# Schemat_ideowy.net
KiCad netlist of a schematic drawn in Altium Designer
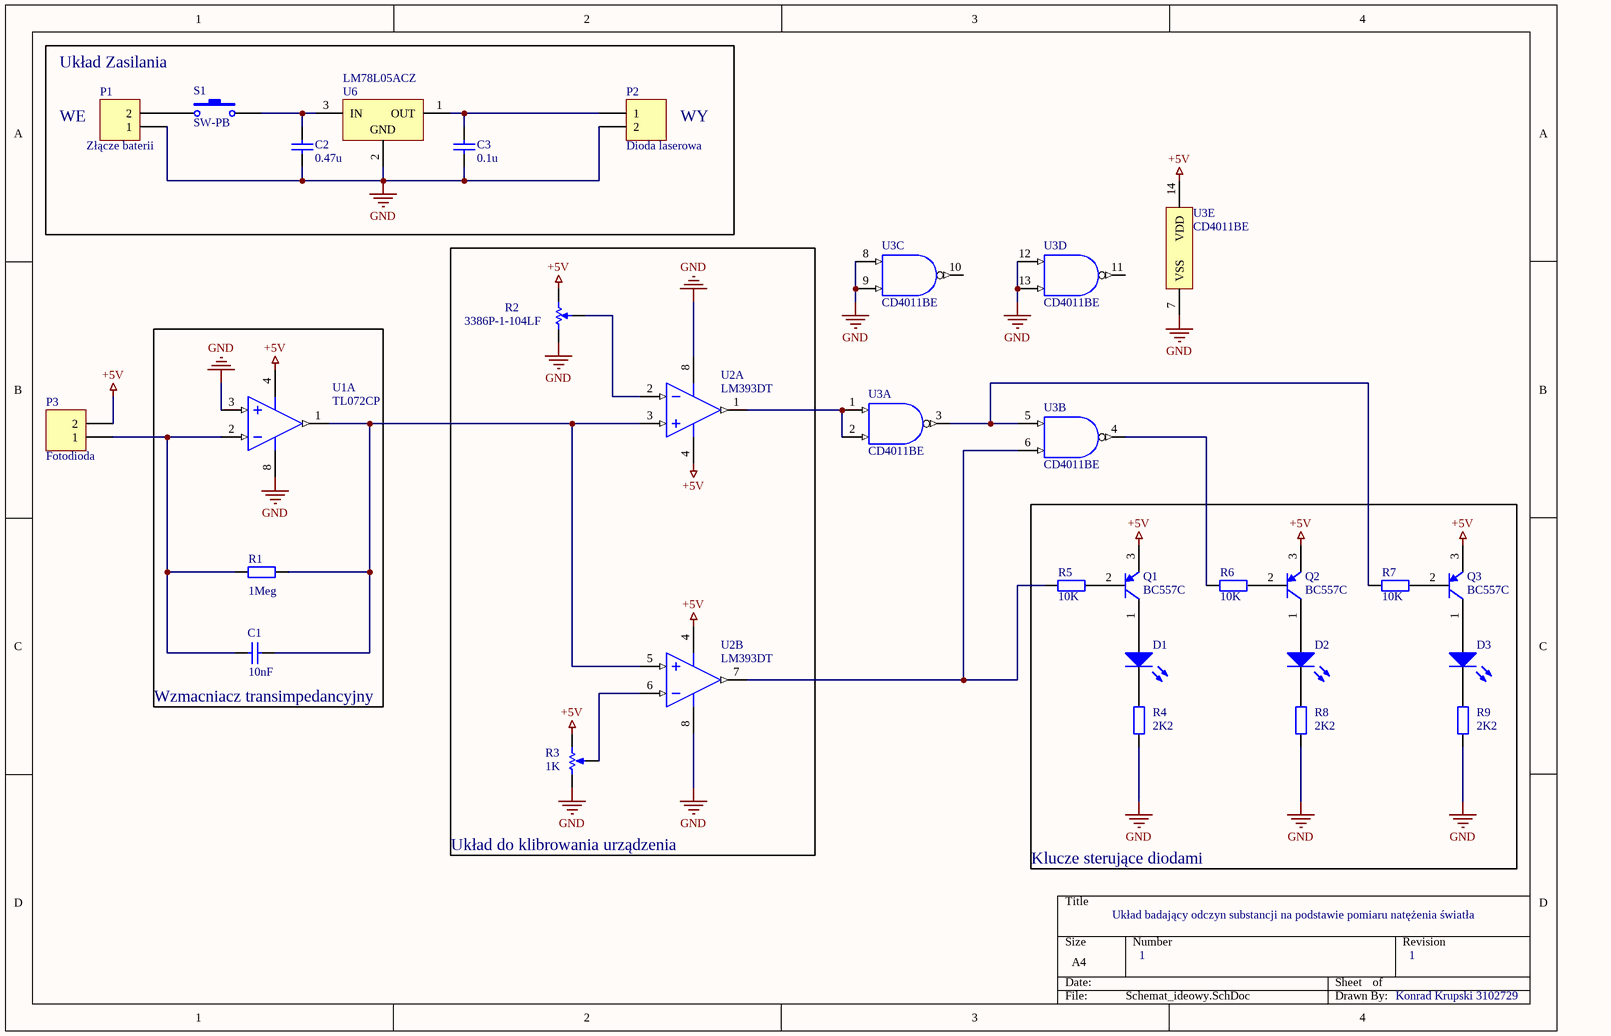
[diagram p0: Schemat_ideowy.SchDoc]

(export (version "E")
  (design (tool "Eeschema 10.0.6"))
  (components
    (comp (ref "C1")
      (value "10nF")
      (footprint "RAD-0.3")
      (description "Capacitor")
      (fields (field (name "Comment") "Cap") (field (name "PUBLISHER") "Altium Limited"))
      (libsource (lib "Miscellaneous Devices") (part "Cap"))
    )
    (comp (ref "C2")
      (value "0.47u")
      (footprint "RAD-0.3")
      (description "Capacitor")
      (fields (field (name "Comment") "Cap") (field (name "PUBLISHER") "Altium Limited"))
      (libsource (lib "Miscellaneous Devices") (part "Cap"))
    )
    (comp (ref "C3")
      (value "0.1u")
      (footprint "RAD-0.3")
      (description "Capacitor")
      (fields (field (name "Comment") "Cap") (field (name "PUBLISHER") "Altium Limited"))
      (libsource (lib "Miscellaneous Devices") (part "Cap"))
    )
    (comp (ref "D1")
      (value "LED3")
      (footprint "3.5X2.8X1.9")
      (description "Typical BLUE SiC LED")
      (fields (field (name "PUBLISHER") "Altium Limited"))
      (libsource (lib "Miscellaneous Devices") (part "LED3"))
    )
    (comp (ref "D2")
      (value "LED2")
      (footprint "3.2X1.6X1.1")
      (description "Typical RED, GREEN, YELLOW, AMBER GaAs LED")
      (fields (field (name "PUBLISHER") "Altium Limited"))
      (libsource (lib "Miscellaneous Devices") (part "LED2"))
    )
    (comp (ref "D3")
      (value "LED2")
      (footprint "3.2X1.6X1.1")
      (description "Typical RED, GREEN, YELLOW, AMBER GaAs LED")
      (fields (field (name "PUBLISHER") "Altium Limited"))
      (libsource (lib "Miscellaneous Devices") (part "LED2"))
    )
    (comp (ref "P1")
      (value "Złącze baterii")
      (footprint "HDR1X2H")
      (description "Header, 2-Pin, Right Angle")
      (fields (field (name "PUBLISHER") "Altium Limited"))
      (libsource (lib "Miscellaneous Connectors") (part "Header 2H"))
    )
    (comp (ref "P2")
      (value "Header 2H")
      (footprint "HDR1X2H")
      (description "Header, 2-Pin, Right Angle")
      (fields (field (name "PUBLISHER") "Altium Limited"))
      (libsource (lib "") (part "Header 2H_1"))
    )
    (comp (ref "P3")
      (value "Fotodioda")
      (footprint "HDR1X2H")
      (description "Header, 2-Pin, Right Angle")
      (fields (field (name "PUBLISHER") "Altium Limited"))
      (libsource (lib "Miscellaneous Connectors") (part "Header 2H"))
    )
    (comp (ref "Q1")
      (value "BC557C")
      (footprint "ONSC-TO-92-3-29-11")
      (description "Amplifier Transistor, PNP Silicon, 3-Pin TO-92, Bulk Box")
      (fields (field (name "MANUFACTURER") "On Semiconductor"))
      (libsource (lib "Altium Content Vault") (part "ONSC-PNP-C1B2E3-3"))
    )
    (comp (ref "Q2")
      (value "BC557C")
      (footprint "ONSC-TO-92-3-29-11")
      (description "Amplifier Transistor, PNP Silicon, 3-Pin TO-92, Bulk Box")
      (fields (field (name "MANUFACTURER") "On Semiconductor"))
      (libsource (lib "Altium Content Vault") (part "ONSC-PNP-C1B2E3-3"))
    )
    (comp (ref "Q3")
      (value "BC557C")
      (footprint "ONSC-TO-92-3-29-11")
      (description "Amplifier Transistor, PNP Silicon, 3-Pin TO-92, Bulk Box")
      (fields (field (name "MANUFACTURER") "On Semiconductor"))
      (libsource (lib "Altium Content Vault") (part "ONSC-PNP-C1B2E3-3"))
    )
    (comp (ref "R1")
      (value "1Meg")
      (footprint "AXIAL-0.4")
      (description "Resistor")
      (fields (field (name "Comment") "Res2") (field (name "PUBLISHER") "Altium Limited"))
      (libsource (lib "") (part "Res2_2"))
    )
    (comp (ref "R2")
      (value "3386P-1-104LF")
      (footprint "BOUR-3386P")
      (fields (field (name "TOLERANCE") "10%") (field (name "MANUFACTURER") "Bourns"))
      (libsource (lib "Altium Content Vault") (part "RES-ADJ-3_A"))
    )
    (comp (ref "R3")
      (value "1K")
      (footprint "VR5")
      (description "Potentiometer")
      (fields (field (name "Comment") "RPot") (field (name "PUBLISHER") "Altium Limited"))
      (libsource (lib "Miscellaneous Devices") (part "RPot"))
    )
    (comp (ref "R4")
      (value "2K2")
      (footprint "AXIAL-0.4")
      (description "Resistor")
      (fields (field (name "Comment") "Res2") (field (name "PUBLISHER") "Altium Limited"))
      (libsource (lib "") (part "Res2_1"))
    )
    (comp (ref "R5")
      (value "10K")
      (footprint "AXIAL-0.4")
      (description "Resistor")
      (fields (field (name "Comment") "Res2") (field (name "PUBLISHER") "Altium Limited"))
      (libsource (lib "Miscellaneous Devices") (part "Res2"))
    )
    (comp (ref "R6")
      (value "10K")
      (footprint "AXIAL-0.4")
      (description "Resistor")
      (fields (field (name "Comment") "Res2") (field (name "PUBLISHER") "Altium Limited"))
      (libsource (lib "Miscellaneous Devices") (part "Res2"))
    )
    (comp (ref "R7")
      (value "10K")
      (footprint "AXIAL-0.4")
      (description "Resistor")
      (fields (field (name "Comment") "Res2") (field (name "PUBLISHER") "Altium Limited"))
      (libsource (lib "Miscellaneous Devices") (part "Res2"))
    )
    (comp (ref "R8")
      (value "2K2")
      (footprint "AXIAL-0.4")
      (description "Resistor")
      (fields (field (name "Comment") "Res2") (field (name "PUBLISHER") "Altium Limited"))
      (libsource (lib "") (part "Res2_1"))
    )
    (comp (ref "R9")
      (value "2K2")
      (footprint "AXIAL-0.4")
      (description "Resistor")
      (fields (field (name "Comment") "Res2") (field (name "PUBLISHER") "Altium Limited"))
      (libsource (lib "") (part "Res2_1"))
    )
    (comp (ref "S1")
      (value "SW-PB")
      (footprint "SPST-2")
      (description "Switch")
      (fields (field (name "PUBLISHER") "Altium Limited"))
      (libsource (lib "Miscellaneous Devices") (part "SW-PB"))
    )
    (comp (ref "U1")
      (value "TL072CP")
      (footprint "P0008A")
      (fields (field (name "MANUFACTURER") "Texas Instruments"))
      (libsource (lib "Altium Content Vault") (part "TI-AMP-D6-2-8_D"))
    )
    (comp (ref "U2")
      (value "LM393DT")
      (footprint "STM-SO-8_D_L")
      (description "Low-Power, Dual-Voltage Comparator, 2 to 36 V, 0 to 70 degC, 8-Pin SOIC (SO), RoHS, Tape and Reel")
      (fields (field (name "MANUFACTURER") "STMicroelectronics"))
      (libsource (lib "Altium Content Vault") (part "STM-LM393-SO8"))
    )
    (comp (ref "U3")
      (value "CD4011BE")
      (footprint "N0014A")
      (description "CMOS Quad 2-Input NAND Gate, N0014A, TUBE")
      (fields
        (field (name "MANUFACTURER") "Texas Instruments")
        (field (name "GENERIC PART NUMBER") "CD4011B")
      )
      (libsource (lib "") (part "TI-NAND-4-2IN-14_A_1"))
    )
    (comp (ref "U6")
      (value "LM78L05ACZ")
      (footprint "Z03A")
      (description "3-Terminal Positive Regulators, 3-pin TO-92")
      (fields (field (name "MANUFACTURER") "National Semiconductor"))
      (libsource (lib "Altium Content Vault") (part "PM-REG-LM78L05-SIL3"))
    )
  )
  (nets
    (net (code "1") (name "+5V") (class "Default")
      (node (ref "P3") (pin "2") (pinfunction "2_2") (pintype "passive"))
      (node (ref "Q1") (pin "3") (pinfunction "E_3") (pintype "passive"))
      (node (ref "Q2") (pin "3") (pinfunction "E_3") (pintype "passive"))
      (node (ref "Q3") (pin "3") (pinfunction "E_3") (pintype "passive"))
      (node (ref "R2") (pin "3") (pinfunction "3_3") (pintype "passive"))
      (node (ref "R3") (pin "2") (pinfunction "BOT_2") (pintype "passive"))
      (node (ref "U1") (pin "4") (pinfunction "VCC-_4") (pintype "power_in"))
      (node (ref "U2") (pin "4") (pinfunction "VCC-_4") (pintype "power_in"))
      (node (ref "U3") (pin "14") (pinfunction "VDD_14") (pintype "power_in"))
    )
    (net (code "2") (name "GND") (class "Default")
      (node (ref "C2") (pin "1") (pinfunction "1_1") (pintype "passive"))
      (node (ref "C3") (pin "1") (pinfunction "1_1") (pintype "passive"))
      (node (ref "P1") (pin "1") (pinfunction "1_1") (pintype "passive"))
      (node (ref "P2") (pin "2") (pinfunction "2_2") (pintype "passive"))
      (node (ref "R2") (pin "1") (pinfunction "1_1") (pintype "passive"))
      (node (ref "R3") (pin "1") (pinfunction "TOP_1") (pintype "passive"))
      (node (ref "R4") (pin "1") (pinfunction "1_1") (pintype "passive"))
      (node (ref "R8") (pin "1") (pinfunction "1_1") (pintype "passive"))
      (node (ref "R9") (pin "1") (pinfunction "1_1") (pintype "passive"))
      (node (ref "U1") (pin "3") (pinfunction "IN1+_3") (pintype "input"))
      (node (ref "U1") (pin "8") (pinfunction "VCC+_8") (pintype "power_in"))
      (node (ref "U2") (pin "8") (pinfunction "VCC+_8") (pintype "power_in"))
      (node (ref "U3") (pin "12") (pinfunction "G_12") (pintype "input"))
      (node (ref "U3") (pin "13") (pinfunction "H_13") (pintype "input"))
      (node (ref "U3") (pin "7") (pinfunction "VSS_7") (pintype "power_in"))
      (node (ref "U3") (pin "8") (pinfunction "E_8") (pintype "input"))
      (node (ref "U3") (pin "9") (pinfunction "F_9") (pintype "input"))
      (node (ref "U6") (pin "2") (pinfunction "GND_2") (pintype "power_in"))
    )
    (net (code "3") (name "Net-(D1-A)") (class "Default")
      (node (ref "D1") (pin "1") (pinfunction "A_1") (pintype "passive"))
      (node (ref "Q1") (pin "1") (pinfunction "C_1") (pintype "passive"))
    )
    (net (code "4") (name "Net-(D1-K)") (class "Default")
      (node (ref "D1") (pin "2") (pinfunction "K_2") (pintype "passive"))
      (node (ref "R4") (pin "2") (pinfunction "2_2") (pintype "passive"))
    )
    (net (code "5") (name "Net-(D2-A)") (class "Default")
      (node (ref "D2") (pin "1") (pinfunction "A_1") (pintype "passive"))
      (node (ref "Q2") (pin "1") (pinfunction "C_1") (pintype "passive"))
    )
    (net (code "6") (name "Net-(D2-K)") (class "Default")
      (node (ref "D2") (pin "2") (pinfunction "K_2") (pintype "passive"))
      (node (ref "R8") (pin "2") (pinfunction "2_2") (pintype "passive"))
    )
    (net (code "7") (name "Net-(D3-A)") (class "Default")
      (node (ref "D3") (pin "1") (pinfunction "A_1") (pintype "passive"))
      (node (ref "Q3") (pin "1") (pinfunction "C_1") (pintype "passive"))
    )
    (net (code "8") (name "Net-(D3-K)") (class "Default")
      (node (ref "D3") (pin "2") (pinfunction "K_2") (pintype "passive"))
      (node (ref "R9") (pin "2") (pinfunction "2_2") (pintype "passive"))
    )
    (net (code "9") (name "Net-(P1-Pad2)") (class "Default")
      (node (ref "P1") (pin "2") (pinfunction "2_2") (pintype "passive"))
      (node (ref "S1") (pin "1") (pinfunction "1_1") (pintype "passive"))
    )
    (net (code "10") (name "Net-(Q1-B)") (class "Default")
      (node (ref "Q1") (pin "2") (pinfunction "B_2") (pintype "passive"))
      (node (ref "R5") (pin "1") (pinfunction "1_1") (pintype "passive"))
    )
    (net (code "11") (name "Net-(Q2-B)") (class "Default")
      (node (ref "Q2") (pin "2") (pinfunction "B_2") (pintype "passive"))
      (node (ref "R6") (pin "1") (pinfunction "1_1") (pintype "passive"))
    )
    (net (code "12") (name "Net-(Q3-B)") (class "Default")
      (node (ref "Q3") (pin "2") (pinfunction "B_2") (pintype "passive"))
      (node (ref "R7") (pin "1") (pinfunction "1_1") (pintype "passive"))
    )
    (net (code "13") (name "Net-(R3-TAP)") (class "Default")
      (node (ref "R3") (pin "3") (pinfunction "TAP_3") (pintype "passive"))
      (node (ref "U2") (pin "6") (pinfunction "IN2-_6") (pintype "input"))
    )
    (net (code "14") (name "Net-(U1A-IN1-)") (class "Default")
      (node (ref "C1") (pin "1") (pinfunction "1_1") (pintype "passive"))
      (node (ref "P3") (pin "1") (pinfunction "1_1") (pintype "passive"))
      (node (ref "R1") (pin "1") (pinfunction "1_1") (pintype "passive"))
      (node (ref "U1") (pin "2") (pinfunction "IN1-_2") (pintype "input"))
    )
    (net (code "15") (name "Net-(U1A-OUT1)") (class "Default")
      (node (ref "C1") (pin "2") (pinfunction "2_2") (pintype "passive"))
      (node (ref "R1") (pin "2") (pinfunction "2_2") (pintype "passive"))
      (node (ref "U1") (pin "1") (pinfunction "OUT1_1") (pintype "output"))
      (node (ref "U2") (pin "3") (pinfunction "IN1+_3") (pintype "input"))
      (node (ref "U2") (pin "5") (pinfunction "IN2+_5") (pintype "input"))
    )
    (net (code "16") (name "Net-(U2A-IN1-)") (class "Default")
      (node (ref "R2") (pin "2") (pinfunction "2_2") (pintype "passive"))
      (node (ref "U2") (pin "2") (pinfunction "IN1-_2") (pintype "input"))
    )
    (net (code "17") (name "Net-(U2A-OUT1)") (class "Default")
      (node (ref "U2") (pin "1") (pinfunction "OUT1_1") (pintype "output"))
      (node (ref "U3") (pin "1") (pinfunction "A_1") (pintype "input"))
      (node (ref "U3") (pin "2") (pinfunction "B_2") (pintype "input"))
    )
    (net (code "18") (name "Net-(U2B-OUT2)") (class "Default")
      (node (ref "R5") (pin "2") (pinfunction "2_2") (pintype "passive"))
      (node (ref "U2") (pin "7") (pinfunction "OUT2_7") (pintype "output"))
      (node (ref "U3") (pin "6") (pinfunction "D_6") (pintype "input"))
    )
    (net (code "19") (name "Net-(U3A-J)") (class "Default")
      (node (ref "R7") (pin "2") (pinfunction "2_2") (pintype "passive"))
      (node (ref "U3") (pin "3") (pinfunction "J_3") (pintype "output"))
      (node (ref "U3") (pin "5") (pinfunction "C_5") (pintype "input"))
    )
    (net (code "20") (name "Net-(U3B-K)") (class "Default")
      (node (ref "R6") (pin "2") (pinfunction "2_2") (pintype "passive"))
      (node (ref "U3") (pin "4") (pinfunction "K_4") (pintype "output"))
    )
    (net (code "21") (name "Net-(U6-IN)") (class "Default")
      (node (ref "C2") (pin "2") (pinfunction "2_2") (pintype "passive"))
      (node (ref "S1") (pin "2") (pinfunction "2_2") (pintype "passive"))
      (node (ref "U6") (pin "3") (pinfunction "IN_3") (pintype "power_in"))
    )
    (net (code "22") (name "Net-(U6-OUT)") (class "Default")
      (node (ref "C3") (pin "2") (pinfunction "2_2") (pintype "passive"))
      (node (ref "P2") (pin "1") (pinfunction "1_1") (pintype "passive"))
      (node (ref "U6") (pin "1") (pinfunction "OUT_1") (pintype "power_in"))
    )
    (net (code "23") (name "unconnected-(U3C-L-Pad10)") (class "Default")
      (node (ref "U3") (pin "10") (pinfunction "L_10") (pintype "output"))
    )
    (net (code "24") (name "unconnected-(U3D-M-Pad11)") (class "Default")
      (node (ref "U3") (pin "11") (pinfunction "M_11") (pintype "output"))
    )
  )
)
